# SparkFun_MIDI_Shield.net
KiCad netlist of a schematic drawn in EAGLE
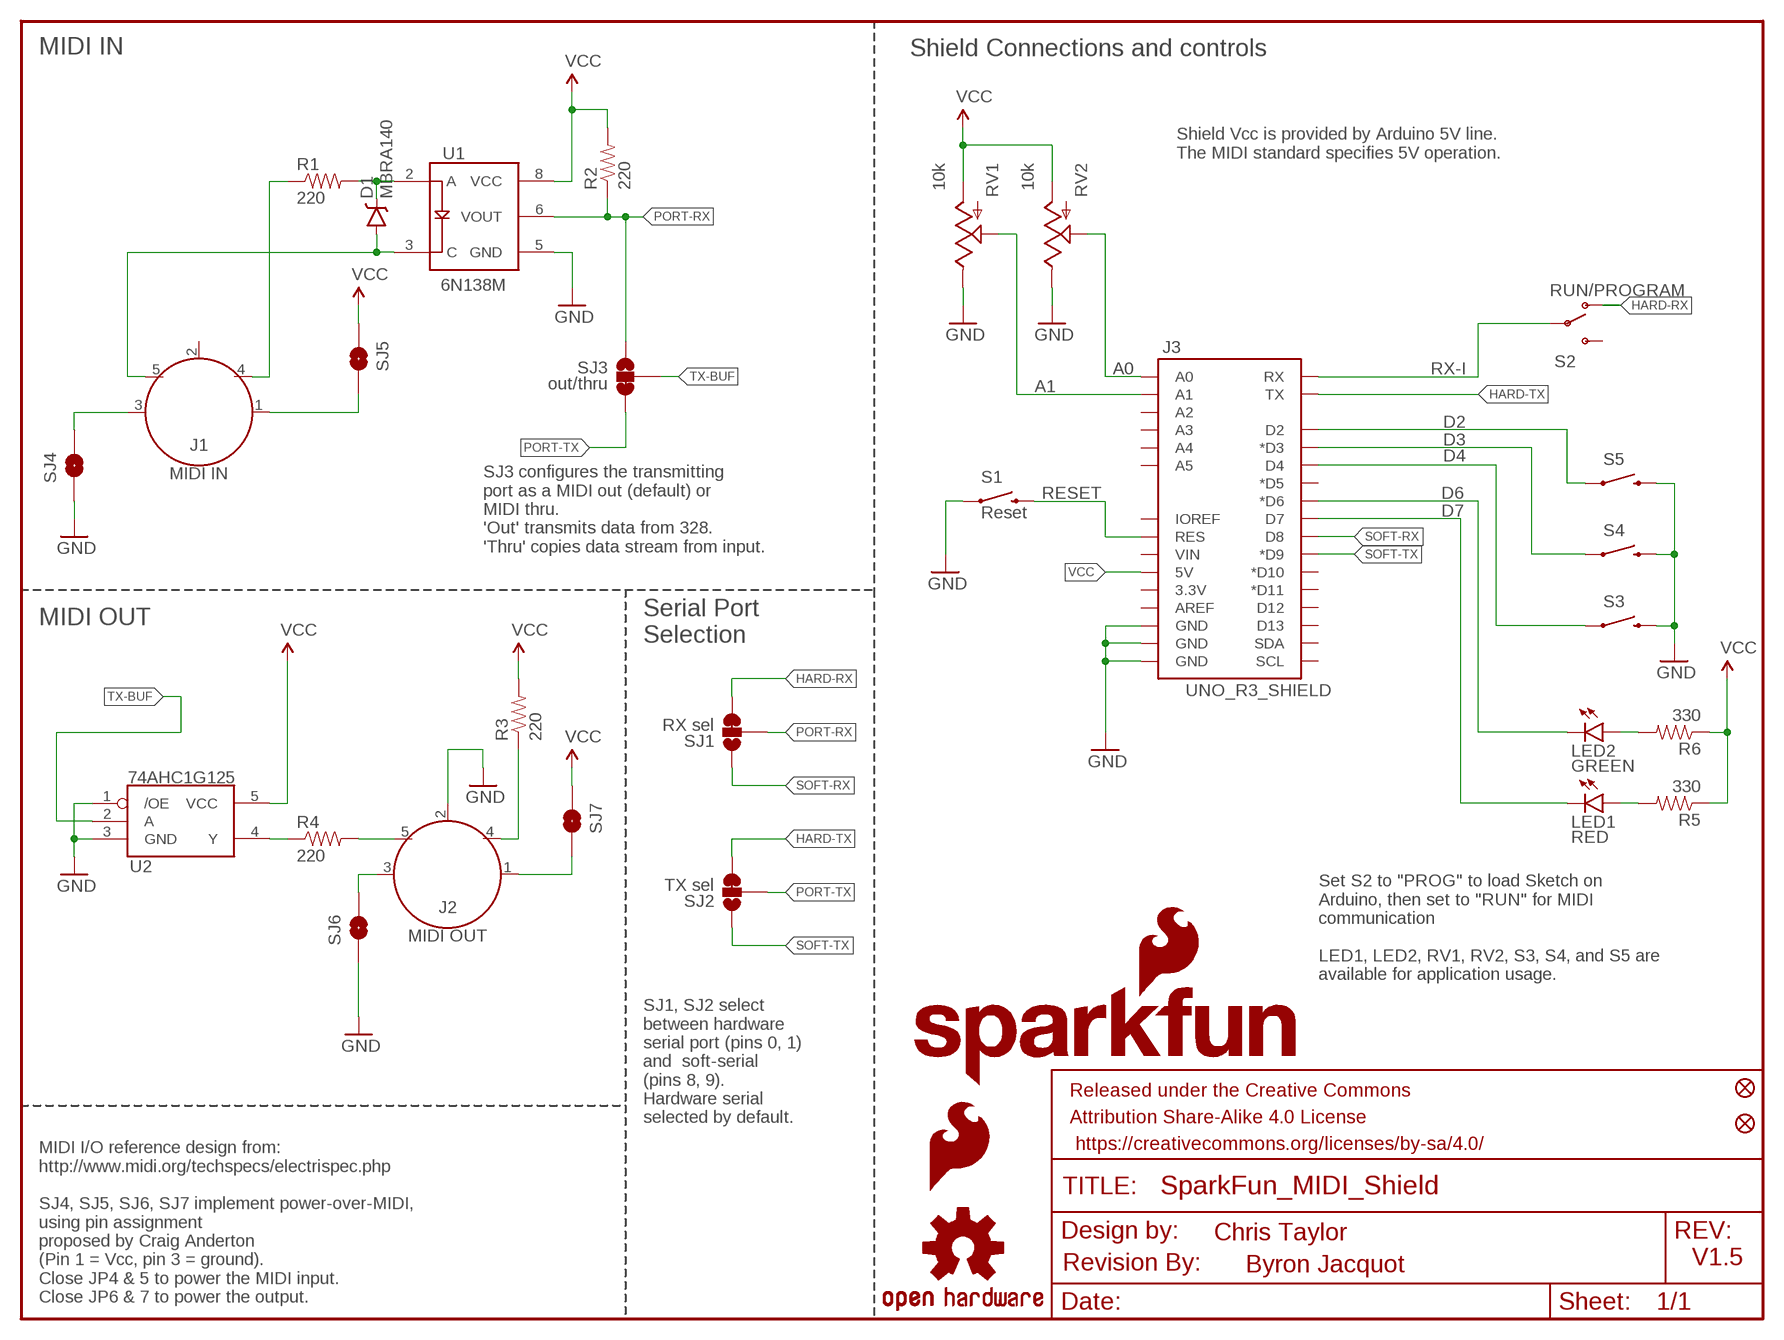
[diagram p0: schematic, sheet 1]

(export (version "E")
  (design (tool "Eeschema 10.0.6"))
  (components
    (comp (ref "D1")
      (value "MBRA140")
      (footprint "eagle-import:SMA-DIODE")
      (libsource (lib "eagle-import") (part "MBRA140"))
    )
    (comp (ref "FID1")
      (value "FIDUCIALUFIDUCIAL")
      (footprint "eagle-import:MICRO-FIDUCIAL")
      (libsource (lib "eagle-import") (part "FIDUCIALUFIDUCIAL"))
    )
    (comp (ref "FID2")
      (value "FIDUCIALUFIDUCIAL")
      (footprint "eagle-import:MICRO-FIDUCIAL")
      (libsource (lib "eagle-import") (part "FIDUCIALUFIDUCIAL"))
    )
    (comp (ref "FRAME1")
      (value "Frame")
      (footprint "eagle-import:CREATIVE_COMMONS")
      (libsource (lib "eagle-import") (part "FRAME-LETTER"))
    )
    (comp (ref "J1")
      (value "MIDI IN")
      (footprint "eagle-import:5-PIN-DIN-RA-PCB-NEW")
      (libsource (lib "eagle-import") (part "5-PIN-CIRCULAR-DINNEW"))
    )
    (comp (ref "J2")
      (value "MIDI OUT")
      (footprint "eagle-import:5-PIN-DIN-RA-PCB-NEW")
      (libsource (lib "eagle-import") (part "5-PIN-CIRCULAR-DINNEW"))
    )
    (comp (ref "J3")
      (value "UNO_R3_SHIELD")
      (footprint "eagle-import:UNO_R3_SHIELD")
      (libsource (lib "eagle-import") (part "ARDUINO_R3_SHIELD"))
    )
    (comp (ref "LED1")
      (value "RED")
      (footprint "eagle-import:LED-0603")
      (libsource (lib "eagle-import") (part "LED-RED0603"))
    )
    (comp (ref "LED2")
      (value "GREEN")
      (footprint "eagle-import:LED-0603")
      (libsource (lib "eagle-import") (part "LED-GREEN0603"))
    )
    (comp (ref "LOGO1")
      (value "SFE_LOGO_NAME_FLAME.2_INCH")
      (footprint "eagle-import:SFE_LOGO_NAME_FLAME_.2")
      (libsource (lib "eagle-import") (part "SFE_LOGO_NAME_FLAME.2_INCH"))
    )
    (comp (ref "LOGO2")
      (value "OSHW-LOGOS")
      (footprint "eagle-import:OSHW-LOGO-S")
      (libsource (lib "eagle-import") (part "OSHW-LOGOS"))
    )
    (comp (ref "LOGO3")
      (value "OSHW-LOGOM")
      (footprint "eagle-import:OSHW-LOGO-M")
      (libsource (lib "eagle-import") (part "OSHW-LOGOM"))
    )
    (comp (ref "LOGO5")
      (value "SFE_LOGO_FLAME.1_INCH")
      (footprint "eagle-import:SFE_LOGO_FLAME_.1")
      (libsource (lib "eagle-import") (part "SFE_LOGO_FLAME.1_INCH"))
    )
    (comp (ref "R1")
      (value "220")
      (footprint "eagle-import:0603-RES")
      (libsource (lib "eagle-import") (part "220OHM-1/10W-1%(0603)"))
    )
    (comp (ref "R2")
      (value "220")
      (footprint "eagle-import:0603-RES")
      (libsource (lib "eagle-import") (part "220OHM-1/10W-1%(0603)"))
    )
    (comp (ref "R3")
      (value "220")
      (footprint "eagle-import:0603-RES")
      (libsource (lib "eagle-import") (part "220OHM-1/10W-1%(0603)"))
    )
    (comp (ref "R4")
      (value "220")
      (footprint "eagle-import:0603-RES")
      (libsource (lib "eagle-import") (part "220OHM-1/10W-1%(0603)"))
    )
    (comp (ref "R5")
      (value "330")
      (footprint "eagle-import:0603-RES")
      (libsource (lib "eagle-import") (part "330OHM1/10W1%(0603)"))
    )
    (comp (ref "R6")
      (value "330")
      (footprint "eagle-import:0603-RES")
      (libsource (lib "eagle-import") (part "330OHM1/10W1%(0603)"))
    )
    (comp (ref "RV1")
      (value "10k")
      (footprint "eagle-import:ALPS_POT")
      (libsource (lib "eagle-import") (part "POT"))
    )
    (comp (ref "RV2")
      (value "10k")
      (footprint "eagle-import:ALPS_POT")
      (libsource (lib "eagle-import") (part "POT"))
    )
    (comp (ref "S1")
      (value "Reset")
      (footprint "eagle-import:TACTILE-SWITCH-SMD")
      (libsource (lib "eagle-import") (part "SWITCH-MOMENTARY-2SMD"))
    )
    (comp (ref "S2")
      (value "RUN/PROGRAM")
      (footprint "eagle-import:AYZ0202")
      (libsource (lib "eagle-import") (part "SWITCH-SPDTSMD"))
    )
    (comp (ref "S3")
      (value "SWITCH-MOMENTARY-212MM")
      (footprint "eagle-import:TACTILE-PTH-12MM")
      (libsource (lib "eagle-import") (part "SWITCH-MOMENTARY-212MM"))
    )
    (comp (ref "S4")
      (value "SWITCH-MOMENTARY-212MM")
      (footprint "eagle-import:TACTILE-PTH-12MM")
      (libsource (lib "eagle-import") (part "SWITCH-MOMENTARY-212MM"))
    )
    (comp (ref "S5")
      (value "SWITCH-MOMENTARY-212MM")
      (footprint "eagle-import:TACTILE-PTH-12MM")
      (libsource (lib "eagle-import") (part "SWITCH-MOMENTARY-212MM"))
    )
    (comp (ref "SJ1")
      (value "RX sel")
      (footprint "eagle-import:PAD-JUMPER-3-2OF3_NC_BY_TRACE_YES_SILK_FULL_BOX")
      (libsource (lib "eagle-import") (part "JUMPER-PAD-3-2OF3_NC_BY_TRACE_SMALL"))
    )
    (comp (ref "SJ2")
      (value "TX sel")
      (footprint "eagle-import:PAD-JUMPER-3-2OF3_NC_BY_TRACE_YES_SILK_FULL_BOX")
      (libsource (lib "eagle-import") (part "JUMPER-PAD-3-2OF3_NC_BY_TRACE_SMALL"))
    )
    (comp (ref "SJ3")
      (value "out/thru")
      (footprint "eagle-import:PAD-JUMPER-3-2OF3_NC_BY_TRACE_YES_SILK_FULL_BOX")
      (libsource (lib "eagle-import") (part "JUMPER-PAD-3-2OF3_NC_BY_TRACE_SMALL"))
    )
    (comp (ref "SJ4")
      (value "JUMPER-PAD-2-NOYES_SILK")
      (footprint "eagle-import:PAD-JUMPER-2-NO_YES_SILK")
      (libsource (lib "eagle-import") (part "JUMPER-PAD-2-NOYES_SILK"))
    )
    (comp (ref "SJ5")
      (value "JUMPER-PAD-2-NOYES_SILK")
      (footprint "eagle-import:PAD-JUMPER-2-NO_YES_SILK")
      (libsource (lib "eagle-import") (part "JUMPER-PAD-2-NOYES_SILK"))
    )
    (comp (ref "SJ6")
      (value "JUMPER-PAD-2-NOYES_SILK")
      (footprint "eagle-import:PAD-JUMPER-2-NO_YES_SILK")
      (libsource (lib "eagle-import") (part "JUMPER-PAD-2-NOYES_SILK"))
    )
    (comp (ref "SJ7")
      (value "JUMPER-PAD-2-NOYES_SILK")
      (footprint "eagle-import:PAD-JUMPER-2-NO_YES_SILK")
      (libsource (lib "eagle-import") (part "JUMPER-PAD-2-NOYES_SILK"))
    )
    (comp (ref "U$1")
      (value "REVISION")
      (footprint "eagle-import:REVISION")
      (libsource (lib "eagle-import") (part "REVISION"))
    )
    (comp (ref "U1")
      (value "6N138M")
      (footprint "eagle-import:8-SMD")
      (libsource (lib "eagle-import") (part "OPTO_DARL_6N138S"))
    )
    (comp (ref "U2")
      (value "74AHC1G125")
      (footprint "eagle-import:SOT23-5")
      (libsource (lib "eagle-import") (part "74AHC1G125"))
    )
  )
  (nets
    (net (code "1") (name "/A0") (class "Default")
      (node (ref "J3") (pin "A0") (pinfunction "A0_A0") (pintype "bidirectional"))
      (node (ref "RV2") (pin "P$2") (pinfunction "S_P$2") (pintype "passive"))
    )
    (net (code "2") (name "/A1") (class "Default")
      (node (ref "J3") (pin "A1") (pinfunction "A1_A1") (pintype "bidirectional"))
      (node (ref "RV1") (pin "P$2") (pinfunction "S_P$2") (pintype "passive"))
    )
    (net (code "3") (name "/D2") (class "Default")
      (node (ref "J3") (pin "D2") (pinfunction "D2_D2") (pintype "bidirectional"))
      (node (ref "S5") (pin "1") (pinfunction "1_1") (pintype "passive"))
    )
    (net (code "4") (name "/D3") (class "Default")
      (node (ref "J3") (pin "D3") (pinfunction "*D3_D3") (pintype "bidirectional"))
      (node (ref "S4") (pin "1") (pinfunction "1_1") (pintype "passive"))
    )
    (net (code "5") (name "/D4") (class "Default")
      (node (ref "J3") (pin "D4") (pinfunction "D4_D4") (pintype "bidirectional"))
      (node (ref "S3") (pin "1") (pinfunction "1_1") (pintype "passive"))
    )
    (net (code "6") (name "/D6") (class "Default")
      (node (ref "J3") (pin "D6") (pinfunction "*D6_D6") (pintype "bidirectional"))
      (node (ref "LED2") (pin "C") (pinfunction "C_C") (pintype "passive"))
    )
    (net (code "7") (name "/D7") (class "Default")
      (node (ref "J3") (pin "D7") (pinfunction "D7_D7") (pintype "bidirectional"))
      (node (ref "LED1") (pin "C") (pinfunction "C_C") (pintype "passive"))
    )
    (net (code "8") (name "/RESET") (class "Default")
      (node (ref "J3") (pin "RES") (pinfunction "RES_RES") (pintype "bidirectional"))
      (node (ref "S1") (pin "3") (pinfunction "2_3") (pintype "passive"))
    )
    (net (code "9") (name "/RX-I") (class "Default")
      (node (ref "J3") (pin "RX") (pinfunction "RX_RX") (pintype "bidirectional"))
      (node (ref "S2") (pin "2") (pinfunction "P_2") (pintype "passive"))
    )
    (net (code "10") (name "GND") (class "Default")
      (node (ref "J2") (pin "2") (pinfunction "2_2") (pintype "bidirectional"))
      (node (ref "J3") (pin "GND@0") (pinfunction "GND_GND@0") (pintype "bidirectional"))
      (node (ref "J3") (pin "GND@1") (pinfunction "GND_GND@1") (pintype "bidirectional"))
      (node (ref "J3") (pin "GND@2") (pinfunction "GND_GND@2") (pintype "bidirectional"))
      (node (ref "RV1") (pin "P$1") (pinfunction "E_P$1") (pintype "passive"))
      (node (ref "RV2") (pin "P$1") (pinfunction "E_P$1") (pintype "passive"))
      (node (ref "S1") (pin "1") (pinfunction "1_1") (pintype "passive"))
      (node (ref "S3") (pin "3") (pinfunction "2_3") (pintype "passive"))
      (node (ref "S4") (pin "3") (pinfunction "2_3") (pintype "passive"))
      (node (ref "S5") (pin "3") (pinfunction "2_3") (pintype "passive"))
      (node (ref "SJ4") (pin "1") (pinfunction "1_1") (pintype "passive"))
      (node (ref "SJ6") (pin "1") (pinfunction "1_1") (pintype "passive"))
      (node (ref "U1") (pin "5") (pinfunction "GND_5") (pintype "bidirectional"))
      (node (ref "U2") (pin "1") (pinfunction "/OE_1") (pintype "bidirectional"))
      (node (ref "U2") (pin "3") (pinfunction "GND_3") (pintype "bidirectional"))
    )
    (net (code "11") (name "HARD-RX") (class "Default")
      (node (ref "S2") (pin "1") (pinfunction "O_1") (pintype "passive"))
      (node (ref "SJ1") (pin "3") (pinfunction "3_3") (pintype "passive"))
    )
    (net (code "12") (name "HARD-TX") (class "Default")
      (node (ref "J3") (pin "TX") (pinfunction "TX_TX") (pintype "bidirectional"))
      (node (ref "SJ2") (pin "3") (pinfunction "3_3") (pintype "passive"))
    )
    (net (code "13") (name "Net-(J1-Pad1)") (class "Default")
      (node (ref "J1") (pin "1") (pinfunction "1_1") (pintype "bidirectional"))
      (node (ref "SJ5") (pin "2") (pinfunction "2_2") (pintype "passive"))
    )
    (net (code "14") (name "Net-(J1-Pad3)") (class "Default")
      (node (ref "J1") (pin "3") (pinfunction "3_3") (pintype "bidirectional"))
      (node (ref "SJ4") (pin "2") (pinfunction "2_2") (pintype "passive"))
    )
    (net (code "15") (name "Net-(J1-Pad4)") (class "Default")
      (node (ref "J1") (pin "4") (pinfunction "4_4") (pintype "bidirectional"))
      (node (ref "R1") (pin "1") (pinfunction "1_1") (pintype "passive"))
    )
    (net (code "16") (name "Net-(J2-Pad1)") (class "Default")
      (node (ref "J2") (pin "1") (pinfunction "1_1") (pintype "bidirectional"))
      (node (ref "SJ7") (pin "2") (pinfunction "2_2") (pintype "passive"))
    )
    (net (code "17") (name "Net-(J2-Pad3)") (class "Default")
      (node (ref "J2") (pin "3") (pinfunction "3_3") (pintype "bidirectional"))
      (node (ref "SJ6") (pin "2") (pinfunction "2_2") (pintype "passive"))
    )
    (net (code "18") (name "Net-(J2-Pad4)") (class "Default")
      (node (ref "J2") (pin "4") (pinfunction "4_4") (pintype "bidirectional"))
      (node (ref "R3") (pin "1") (pinfunction "1_1") (pintype "passive"))
    )
    (net (code "19") (name "Net-(J2-Pad5)") (class "Default")
      (node (ref "J2") (pin "5") (pinfunction "5_5") (pintype "bidirectional"))
      (node (ref "R4") (pin "2") (pinfunction "2_2") (pintype "passive"))
    )
    (net (code "20") (name "Net-(LED1-PadA)") (class "Default")
      (node (ref "LED1") (pin "A") (pinfunction "A_A") (pintype "passive"))
      (node (ref "R5") (pin "2") (pinfunction "2_2") (pintype "passive"))
    )
    (net (code "21") (name "Net-(LED2-PadA)") (class "Default")
      (node (ref "LED2") (pin "A") (pinfunction "A_A") (pintype "passive"))
      (node (ref "R6") (pin "2") (pinfunction "2_2") (pintype "passive"))
    )
    (net (code "22") (name "Net-(U1-A)") (class "Default")
      (node (ref "D1") (pin "C") (pinfunction "C_C") (pintype "passive"))
      (node (ref "R1") (pin "2") (pinfunction "2_2") (pintype "passive"))
      (node (ref "U1") (pin "2") (pinfunction "A_2") (pintype "bidirectional"))
    )
    (net (code "23") (name "Net-(U1-C)") (class "Default")
      (node (ref "D1") (pin "A") (pinfunction "A_A") (pintype "passive"))
      (node (ref "J1") (pin "5") (pinfunction "5_5") (pintype "bidirectional"))
      (node (ref "U1") (pin "3") (pinfunction "C_3") (pintype "bidirectional"))
    )
    (net (code "24") (name "Net-(U2-Y)") (class "Default")
      (node (ref "R4") (pin "1") (pinfunction "1_1") (pintype "passive"))
      (node (ref "U2") (pin "4") (pinfunction "Y_4") (pintype "bidirectional"))
    )
    (net (code "25") (name "PORT-RX") (class "Default")
      (node (ref "R2") (pin "1") (pinfunction "1_1") (pintype "passive"))
      (node (ref "SJ1") (pin "2") (pinfunction "2_2") (pintype "passive"))
      (node (ref "SJ3") (pin "1") (pinfunction "1_1") (pintype "passive"))
      (node (ref "U1") (pin "6") (pinfunction "VOUT_6") (pintype "bidirectional"))
    )
    (net (code "26") (name "PORT-TX") (class "Default")
      (node (ref "SJ2") (pin "2") (pinfunction "2_2") (pintype "passive"))
      (node (ref "SJ3") (pin "3") (pinfunction "3_3") (pintype "passive"))
    )
    (net (code "27") (name "SOFT-RX") (class "Default")
      (node (ref "J3") (pin "D8") (pinfunction "D8_D8") (pintype "bidirectional"))
      (node (ref "SJ1") (pin "1") (pinfunction "1_1") (pintype "passive"))
    )
    (net (code "28") (name "SOFT-TX") (class "Default")
      (node (ref "J3") (pin "D9") (pinfunction "*D9_D9") (pintype "bidirectional"))
      (node (ref "SJ2") (pin "1") (pinfunction "1_1") (pintype "passive"))
    )
    (net (code "29") (name "TX-BUF") (class "Default")
      (node (ref "SJ3") (pin "2") (pinfunction "2_2") (pintype "passive"))
      (node (ref "U2") (pin "2") (pinfunction "A_2") (pintype "bidirectional"))
    )
    (net (code "30") (name "VCC") (class "Default")
      (node (ref "J3") (pin "5V") (pinfunction "5V_5V") (pintype "bidirectional"))
      (node (ref "R2") (pin "2") (pinfunction "2_2") (pintype "passive"))
      (node (ref "R3") (pin "2") (pinfunction "2_2") (pintype "passive"))
      (node (ref "R5") (pin "1") (pinfunction "1_1") (pintype "passive"))
      (node (ref "R6") (pin "1") (pinfunction "1_1") (pintype "passive"))
      (node (ref "RV1") (pin "P$3") (pinfunction "A_P$3") (pintype "passive"))
      (node (ref "RV2") (pin "P$3") (pinfunction "A_P$3") (pintype "passive"))
      (node (ref "SJ5") (pin "1") (pinfunction "1_1") (pintype "passive"))
      (node (ref "SJ7") (pin "1") (pinfunction "1_1") (pintype "passive"))
      (node (ref "U1") (pin "8") (pinfunction "VCC_8") (pintype "bidirectional"))
      (node (ref "U2") (pin "5") (pinfunction "VCC_5") (pintype "bidirectional"))
    )
    (net (code "31") (name "unconnected-(J1-Pad2)") (class "Default")
      (node (ref "J1") (pin "2") (pinfunction "2_2") (pintype "bidirectional"))
    )
    (net (code "32") (name "unconnected-(J3-*D5-PadD5)") (class "Default")
      (node (ref "J3") (pin "D5") (pinfunction "*D5_D5") (pintype "bidirectional"))
    )
    (net (code "33") (name "unconnected-(J3-*D10-PadD10)") (class "Default")
      (node (ref "J3") (pin "D10") (pinfunction "*D10_D10") (pintype "bidirectional"))
    )
    (net (code "34") (name "unconnected-(J3-*D11-PadD11)") (class "Default")
      (node (ref "J3") (pin "D11") (pinfunction "*D11_D11") (pintype "bidirectional"))
    )
    (net (code "35") (name "unconnected-(J3-Pad3.3V)") (class "Default")
      (node (ref "J3") (pin "3.3V") (pinfunction "3.3V_3.3V") (pintype "bidirectional"))
    )
    (net (code "36") (name "unconnected-(J3-PadA2)") (class "Default")
      (node (ref "J3") (pin "A2") (pinfunction "A2_A2") (pintype "bidirectional"))
    )
    (net (code "37") (name "unconnected-(J3-PadA3)") (class "Default")
      (node (ref "J3") (pin "A3") (pinfunction "A3_A3") (pintype "bidirectional"))
    )
    (net (code "38") (name "unconnected-(J3-PadA4)") (class "Default")
      (node (ref "J3") (pin "A4") (pinfunction "A4_A4") (pintype "bidirectional"))
    )
    (net (code "39") (name "unconnected-(J3-PadA5)") (class "Default")
      (node (ref "J3") (pin "A5") (pinfunction "A5_A5") (pintype "bidirectional"))
    )
    (net (code "40") (name "unconnected-(J3-PadAREF)") (class "Default")
      (node (ref "J3") (pin "AREF") (pinfunction "AREF_AREF") (pintype "bidirectional"))
    )
    (net (code "41") (name "unconnected-(J3-PadD12)") (class "Default")
      (node (ref "J3") (pin "D12") (pinfunction "D12_D12") (pintype "bidirectional"))
    )
    (net (code "42") (name "unconnected-(J3-PadD13)") (class "Default")
      (node (ref "J3") (pin "D13") (pinfunction "D13_D13") (pintype "bidirectional"))
    )
    (net (code "43") (name "unconnected-(J3-PadIOREF)") (class "Default")
      (node (ref "J3") (pin "IOREF") (pinfunction "IOREF_IOREF") (pintype "bidirectional"))
    )
    (net (code "44") (name "unconnected-(J3-PadSCL)") (class "Default")
      (node (ref "J3") (pin "SCL") (pinfunction "SCL_SCL") (pintype "bidirectional"))
    )
    (net (code "45") (name "unconnected-(J3-PadSDA)") (class "Default")
      (node (ref "J3") (pin "SDA") (pinfunction "SDA_SDA") (pintype "bidirectional"))
    )
    (net (code "46") (name "unconnected-(J3-PadVIN)") (class "Default")
      (node (ref "J3") (pin "VIN") (pinfunction "VIN_VIN") (pintype "bidirectional"))
    )
    (net (code "47") (name "unconnected-(S2-S-Pad3)") (class "Default")
      (node (ref "S2") (pin "3") (pinfunction "S_3") (pintype "passive"))
    )
  )
)
